# SparkFun_Pressure_Breakout-MPL115A1.net
KiCad netlist of a schematic drawn in EAGLE
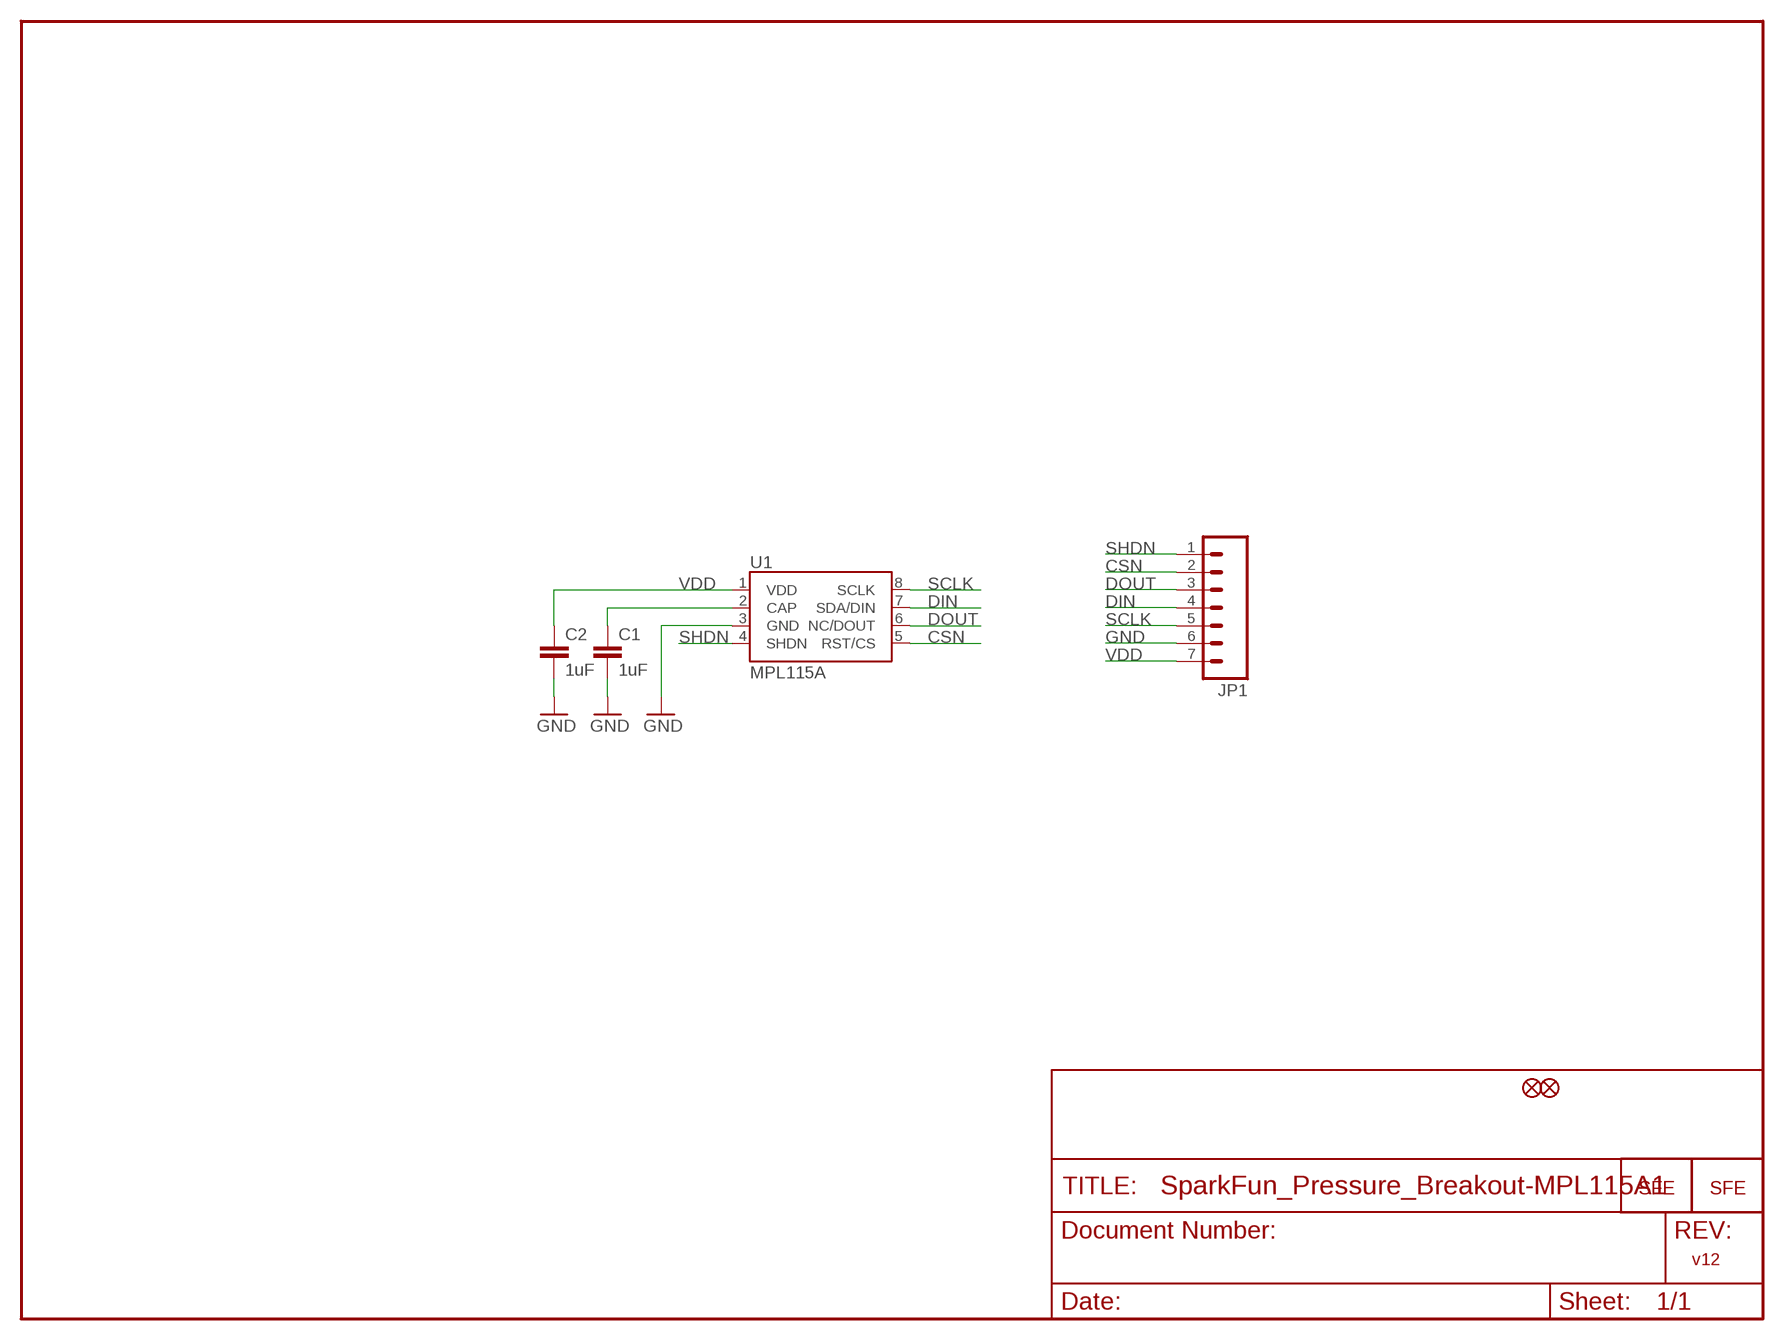
[diagram p0: schematic, sheet 1]

(export (version "E")
  (design (tool "Eeschema 10.0.6"))
  (components
    (comp (ref "C1")
      (value "1uF")
      (footprint "eagle-import:0603-CAP")
      (libsource (lib "eagle-import") (part "CAP0603-CAP"))
    )
    (comp (ref "C2")
      (value "1uF")
      (footprint "eagle-import:0603-CAP")
      (libsource (lib "eagle-import") (part "CAP0603-CAP"))
    )
    (comp (ref "FID1")
      (value "FIDUCIALUFIDUCIAL")
      (footprint "eagle-import:MICRO-FIDUCIAL")
      (libsource (lib "eagle-import") (part "FIDUCIALUFIDUCIAL"))
    )
    (comp (ref "FID2")
      (value "FIDUCIALUFIDUCIAL")
      (footprint "eagle-import:MICRO-FIDUCIAL")
      (libsource (lib "eagle-import") (part "FIDUCIALUFIDUCIAL"))
    )
    (comp (ref "JP1")
      (value "M07")
      (footprint "eagle-import:1X07")
      (libsource (lib "eagle-import") (part "M07"))
    )
    (comp (ref "JP2")
      (value "LOGO-SFESK")
      (footprint "eagle-import:SFE-LOGO-FLAME")
      (libsource (lib "eagle-import") (part "LOGO-SFESK"))
    )
    (comp (ref "JP3")
      (value "LOGO-SFENW2")
      (footprint "eagle-import:SFE-NEW-WEB")
      (libsource (lib "eagle-import") (part "LOGO-SFENW2"))
    )
    (comp (ref "U1")
      (value "MPL115A")
      (footprint "eagle-import:LGA8")
      (libsource (lib "eagle-import") (part "MPL115A"))
    )
  )
  (nets
    (net (code "1") (name "/CSN") (class "Default")
      (node (ref "JP1") (pin "2") (pinfunction "2_2") (pintype "passive"))
      (node (ref "U1") (pin "5") (pinfunction "RST/CS_5") (pintype "bidirectional"))
    )
    (net (code "2") (name "/DIN") (class "Default")
      (node (ref "JP1") (pin "4") (pinfunction "4_4") (pintype "passive"))
      (node (ref "U1") (pin "7") (pinfunction "SDA/DIN_7") (pintype "bidirectional"))
    )
    (net (code "3") (name "/DOUT") (class "Default")
      (node (ref "JP1") (pin "3") (pinfunction "3_3") (pintype "passive"))
      (node (ref "U1") (pin "6") (pinfunction "NC/DOUT_6") (pintype "bidirectional"))
    )
    (net (code "4") (name "/SCLK") (class "Default")
      (node (ref "JP1") (pin "5") (pinfunction "5_5") (pintype "passive"))
      (node (ref "U1") (pin "8") (pinfunction "SCLK_8") (pintype "bidirectional"))
    )
    (net (code "5") (name "/SHDN") (class "Default")
      (node (ref "JP1") (pin "1") (pinfunction "1_1") (pintype "passive"))
      (node (ref "U1") (pin "4") (pinfunction "SHDN_4") (pintype "bidirectional"))
    )
    (net (code "6") (name "/VDD") (class "Default")
      (node (ref "C2") (pin "1") (pinfunction "1_1") (pintype "passive"))
      (node (ref "JP1") (pin "7") (pinfunction "7_7") (pintype "passive"))
      (node (ref "U1") (pin "1") (pinfunction "VDD_1") (pintype "bidirectional"))
    )
    (net (code "7") (name "GND") (class "Default")
      (node (ref "C1") (pin "2") (pinfunction "2_2") (pintype "passive"))
      (node (ref "C2") (pin "2") (pinfunction "2_2") (pintype "passive"))
      (node (ref "JP1") (pin "6") (pinfunction "6_6") (pintype "passive"))
      (node (ref "U1") (pin "3") (pinfunction "GND_3") (pintype "bidirectional"))
    )
    (net (code "8") (name "Net-(U1-CAP)") (class "Default")
      (node (ref "C1") (pin "1") (pinfunction "1_1") (pintype "passive"))
      (node (ref "U1") (pin "2") (pinfunction "CAP_2") (pintype "bidirectional"))
    )
  )
)
